# Sheet4.net
KiCad netlist of a schematic drawn in Altium Designer
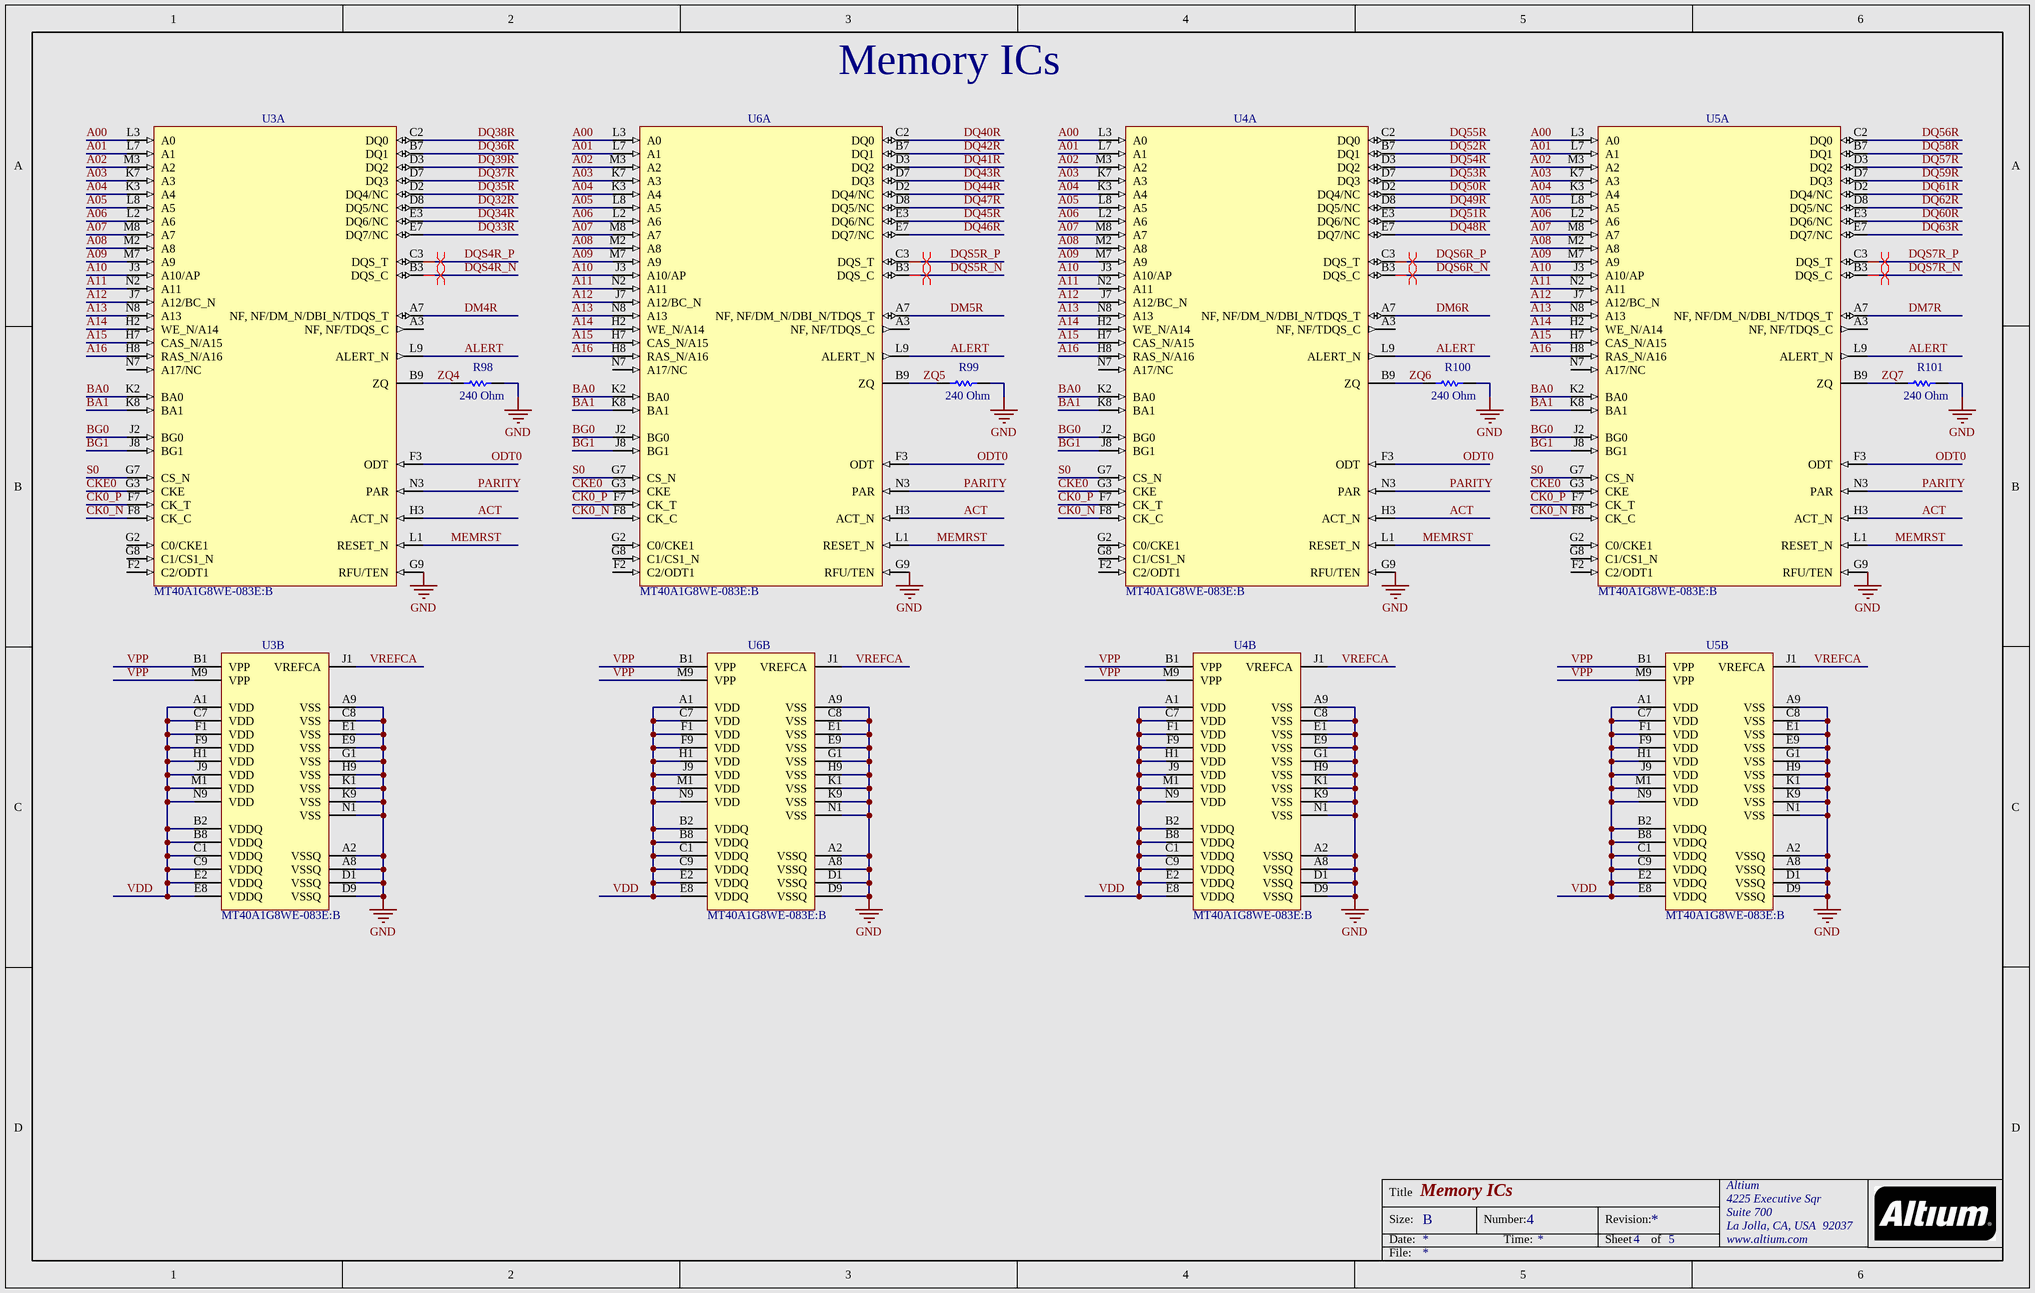
[diagram p0: Sheet4.SchDoc]

(export (version "E")
  (design (tool "Eeschema 10.0.6"))
  (components
    (comp (ref "R98")
      (value "ERJ-2GEJ241x")
      (footprint "RESC1005X40X25ML05T05")
      (description "Chip Resistor, 240 Ohm, +/- 5%, 100 mW, -55 to 155 degC, 0402 (1005 Metric), RoHS, Tape and Reel")
      (fields
        (field (name "RESISTANCE") "240 Ohm")
        (field (name "TOLERANCE") "5%")
        (field (name "MANUFACTURER") "Basic Passives")
      )
      (libsource (lib "Altium Content Vault") (part "CMP-2002-00493-3"))
    )
    (comp (ref "R99")
      (value "ERJ-2GEJ241x")
      (footprint "RESC1005X40X25ML05T05")
      (description "Chip Resistor, 240 Ohm, +/- 5%, 100 mW, -55 to 155 degC, 0402 (1005 Metric), RoHS, Tape and Reel")
      (fields
        (field (name "RESISTANCE") "240 Ohm")
        (field (name "TOLERANCE") "5%")
        (field (name "MANUFACTURER") "Basic Passives")
      )
      (libsource (lib "Altium Content Vault") (part "CMP-2002-00493-3"))
    )
    (comp (ref "R100")
      (value "ERJ-2GEJ241x")
      (footprint "RESC1005X40X25ML05T05")
      (description "Chip Resistor, 240 Ohm, +/- 5%, 100 mW, -55 to 155 degC, 0402 (1005 Metric), RoHS, Tape and Reel")
      (fields
        (field (name "RESISTANCE") "240 Ohm")
        (field (name "TOLERANCE") "5%")
        (field (name "MANUFACTURER") "Basic Passives")
      )
      (libsource (lib "Altium Content Vault") (part "CMP-2002-00493-3"))
    )
    (comp (ref "R101")
      (value "ERJ-2GEJ241x")
      (footprint "RESC1005X40X25ML05T05")
      (description "Chip Resistor, 240 Ohm, +/- 5%, 100 mW, -55 to 155 degC, 0402 (1005 Metric), RoHS, Tape and Reel")
      (fields
        (field (name "RESISTANCE") "240 Ohm")
        (field (name "TOLERANCE") "5%")
        (field (name "MANUFACTURER") "Basic Passives")
      )
      (libsource (lib "Altium Content Vault") (part "CMP-2002-00493-3"))
    )
    (comp (ref "U3")
      (value "MT40A1G8WE-083E:B")
      (footprint "MICT-WE-78")
      (description "8 Gb DDR4 SDRAM, 1 Gig x 8, 1.2 V, 0 to 95 degC, 78-Ball FBGA (WE), RoHS")
      (libsource (lib "Altium Content Vault") (part "CMP-1738-00001-1"))
    )
    (comp (ref "U4")
      (value "MT40A1G8WE-083E:B")
      (footprint "MICT-WE-78")
      (description "8 Gb DDR4 SDRAM, 1 Gig x 8, 1.2 V, 0 to 95 degC, 78-Ball FBGA (WE), RoHS")
      (libsource (lib "Altium Content Vault") (part "CMP-1738-00001-1"))
    )
    (comp (ref "U5")
      (value "MT40A1G8WE-083E:B")
      (footprint "MICT-WE-78")
      (description "8 Gb DDR4 SDRAM, 1 Gig x 8, 1.2 V, 0 to 95 degC, 78-Ball FBGA (WE), RoHS")
      (libsource (lib "Altium Content Vault") (part "CMP-1738-00001-1"))
    )
    (comp (ref "U6")
      (value "MT40A1G8WE-083E:B")
      (footprint "MICT-WE-78")
      (description "8 Gb DDR4 SDRAM, 1 Gig x 8, 1.2 V, 0 to 95 degC, 78-Ball FBGA (WE), RoHS")
      (libsource (lib "Altium Content Vault") (part "CMP-1738-00001-1"))
    )
  )
  (nets
    (net (code "1") (name "/A00") (class "Default")
      (node (ref "U3") (pin "L3") (pinfunction "A0_L3") (pintype "input"))
      (node (ref "U4") (pin "L3") (pinfunction "A0_L3") (pintype "input"))
      (node (ref "U5") (pin "L3") (pinfunction "A0_L3") (pintype "input"))
      (node (ref "U6") (pin "L3") (pinfunction "A0_L3") (pintype "input"))
    )
    (net (code "2") (name "/A01") (class "Default")
      (node (ref "U3") (pin "L7") (pinfunction "A1_L7") (pintype "input"))
      (node (ref "U4") (pin "L7") (pinfunction "A1_L7") (pintype "input"))
      (node (ref "U5") (pin "L7") (pinfunction "A1_L7") (pintype "input"))
      (node (ref "U6") (pin "L7") (pinfunction "A1_L7") (pintype "input"))
    )
    (net (code "3") (name "/A02") (class "Default")
      (node (ref "U3") (pin "M3") (pinfunction "A2_M3") (pintype "input"))
      (node (ref "U4") (pin "M3") (pinfunction "A2_M3") (pintype "input"))
      (node (ref "U5") (pin "M3") (pinfunction "A2_M3") (pintype "input"))
      (node (ref "U6") (pin "M3") (pinfunction "A2_M3") (pintype "input"))
    )
    (net (code "4") (name "/A03") (class "Default")
      (node (ref "U3") (pin "K7") (pinfunction "A3_K7") (pintype "input"))
      (node (ref "U4") (pin "K7") (pinfunction "A3_K7") (pintype "input"))
      (node (ref "U5") (pin "K7") (pinfunction "A3_K7") (pintype "input"))
      (node (ref "U6") (pin "K7") (pinfunction "A3_K7") (pintype "input"))
    )
    (net (code "5") (name "/A04") (class "Default")
      (node (ref "U3") (pin "K3") (pinfunction "A4_K3") (pintype "input"))
      (node (ref "U4") (pin "K3") (pinfunction "A4_K3") (pintype "input"))
      (node (ref "U5") (pin "K3") (pinfunction "A4_K3") (pintype "input"))
      (node (ref "U6") (pin "K3") (pinfunction "A4_K3") (pintype "input"))
    )
    (net (code "6") (name "/A05") (class "Default")
      (node (ref "U3") (pin "L8") (pinfunction "A5_L8") (pintype "input"))
      (node (ref "U4") (pin "L8") (pinfunction "A5_L8") (pintype "input"))
      (node (ref "U5") (pin "L8") (pinfunction "A5_L8") (pintype "input"))
      (node (ref "U6") (pin "L8") (pinfunction "A5_L8") (pintype "input"))
    )
    (net (code "7") (name "/A06") (class "Default")
      (node (ref "U3") (pin "L2") (pinfunction "A6_L2") (pintype "input"))
      (node (ref "U4") (pin "L2") (pinfunction "A6_L2") (pintype "input"))
      (node (ref "U5") (pin "L2") (pinfunction "A6_L2") (pintype "input"))
      (node (ref "U6") (pin "L2") (pinfunction "A6_L2") (pintype "input"))
    )
    (net (code "8") (name "/A07") (class "Default")
      (node (ref "U3") (pin "M8") (pinfunction "A7_M8") (pintype "input"))
      (node (ref "U4") (pin "M8") (pinfunction "A7_M8") (pintype "input"))
      (node (ref "U5") (pin "M8") (pinfunction "A7_M8") (pintype "input"))
      (node (ref "U6") (pin "M8") (pinfunction "A7_M8") (pintype "input"))
    )
    (net (code "9") (name "/A08") (class "Default")
      (node (ref "U3") (pin "M2") (pinfunction "A8_M2") (pintype "input"))
      (node (ref "U4") (pin "M2") (pinfunction "A8_M2") (pintype "input"))
      (node (ref "U5") (pin "M2") (pinfunction "A8_M2") (pintype "input"))
      (node (ref "U6") (pin "M2") (pinfunction "A8_M2") (pintype "input"))
    )
    (net (code "10") (name "/A09") (class "Default")
      (node (ref "U3") (pin "M7") (pinfunction "A9_M7") (pintype "input"))
      (node (ref "U4") (pin "M7") (pinfunction "A9_M7") (pintype "input"))
      (node (ref "U5") (pin "M7") (pinfunction "A9_M7") (pintype "input"))
      (node (ref "U6") (pin "M7") (pinfunction "A9_M7") (pintype "input"))
    )
    (net (code "11") (name "/A10") (class "Default")
      (node (ref "U3") (pin "J3") (pinfunction "A10/AP_J3") (pintype "input"))
      (node (ref "U4") (pin "J3") (pinfunction "A10/AP_J3") (pintype "input"))
      (node (ref "U5") (pin "J3") (pinfunction "A10/AP_J3") (pintype "input"))
      (node (ref "U6") (pin "J3") (pinfunction "A10/AP_J3") (pintype "input"))
    )
    (net (code "12") (name "/A11") (class "Default")
      (node (ref "U3") (pin "N2") (pinfunction "A11_N2") (pintype "input"))
      (node (ref "U4") (pin "N2") (pinfunction "A11_N2") (pintype "input"))
      (node (ref "U5") (pin "N2") (pinfunction "A11_N2") (pintype "input"))
      (node (ref "U6") (pin "N2") (pinfunction "A11_N2") (pintype "input"))
    )
    (net (code "13") (name "/A12") (class "Default")
      (node (ref "U3") (pin "J7") (pinfunction "A12/BC_N_J7") (pintype "input"))
      (node (ref "U4") (pin "J7") (pinfunction "A12/BC_N_J7") (pintype "input"))
      (node (ref "U5") (pin "J7") (pinfunction "A12/BC_N_J7") (pintype "input"))
      (node (ref "U6") (pin "J7") (pinfunction "A12/BC_N_J7") (pintype "input"))
    )
    (net (code "14") (name "/A13") (class "Default")
      (node (ref "U3") (pin "N8") (pinfunction "A13_N8") (pintype "input"))
      (node (ref "U4") (pin "N8") (pinfunction "A13_N8") (pintype "input"))
      (node (ref "U5") (pin "N8") (pinfunction "A13_N8") (pintype "input"))
      (node (ref "U6") (pin "N8") (pinfunction "A13_N8") (pintype "input"))
    )
    (net (code "15") (name "/A14") (class "Default")
      (node (ref "U3") (pin "H2") (pinfunction "WE_N/A14_H2") (pintype "input"))
      (node (ref "U4") (pin "H2") (pinfunction "WE_N/A14_H2") (pintype "input"))
      (node (ref "U5") (pin "H2") (pinfunction "WE_N/A14_H2") (pintype "input"))
      (node (ref "U6") (pin "H2") (pinfunction "WE_N/A14_H2") (pintype "input"))
    )
    (net (code "16") (name "/A15") (class "Default")
      (node (ref "U3") (pin "H7") (pinfunction "CAS_N/A15_H7") (pintype "input"))
      (node (ref "U4") (pin "H7") (pinfunction "CAS_N/A15_H7") (pintype "input"))
      (node (ref "U5") (pin "H7") (pinfunction "CAS_N/A15_H7") (pintype "input"))
      (node (ref "U6") (pin "H7") (pinfunction "CAS_N/A15_H7") (pintype "input"))
    )
    (net (code "17") (name "/A16") (class "Default")
      (node (ref "U3") (pin "H8") (pinfunction "RAS_N/A16_H8") (pintype "input"))
      (node (ref "U4") (pin "H8") (pinfunction "RAS_N/A16_H8") (pintype "input"))
      (node (ref "U5") (pin "H8") (pinfunction "RAS_N/A16_H8") (pintype "input"))
      (node (ref "U6") (pin "H8") (pinfunction "RAS_N/A16_H8") (pintype "input"))
    )
    (net (code "18") (name "/ACT") (class "Default")
      (node (ref "U3") (pin "H3") (pinfunction "ACT_N_H3") (pintype "input"))
      (node (ref "U4") (pin "H3") (pinfunction "ACT_N_H3") (pintype "input"))
      (node (ref "U5") (pin "H3") (pinfunction "ACT_N_H3") (pintype "input"))
      (node (ref "U6") (pin "H3") (pinfunction "ACT_N_H3") (pintype "input"))
    )
    (net (code "19") (name "/ALERT") (class "Default")
      (node (ref "U3") (pin "L9") (pinfunction "ALERT_N_L9") (pintype "output"))
      (node (ref "U4") (pin "L9") (pinfunction "ALERT_N_L9") (pintype "output"))
      (node (ref "U5") (pin "L9") (pinfunction "ALERT_N_L9") (pintype "output"))
      (node (ref "U6") (pin "L9") (pinfunction "ALERT_N_L9") (pintype "output"))
    )
    (net (code "20") (name "/BA0") (class "Default")
      (node (ref "U3") (pin "K2") (pinfunction "BA0_K2") (pintype "input"))
      (node (ref "U4") (pin "K2") (pinfunction "BA0_K2") (pintype "input"))
      (node (ref "U5") (pin "K2") (pinfunction "BA0_K2") (pintype "input"))
      (node (ref "U6") (pin "K2") (pinfunction "BA0_K2") (pintype "input"))
    )
    (net (code "21") (name "/BA1") (class "Default")
      (node (ref "U3") (pin "K8") (pinfunction "BA1_K8") (pintype "input"))
      (node (ref "U4") (pin "K8") (pinfunction "BA1_K8") (pintype "input"))
      (node (ref "U5") (pin "K8") (pinfunction "BA1_K8") (pintype "input"))
      (node (ref "U6") (pin "K8") (pinfunction "BA1_K8") (pintype "input"))
    )
    (net (code "22") (name "/BG0") (class "Default")
      (node (ref "U3") (pin "J2") (pinfunction "BG0_J2") (pintype "input"))
      (node (ref "U4") (pin "J2") (pinfunction "BG0_J2") (pintype "input"))
      (node (ref "U5") (pin "J2") (pinfunction "BG0_J2") (pintype "input"))
      (node (ref "U6") (pin "J2") (pinfunction "BG0_J2") (pintype "input"))
    )
    (net (code "23") (name "/BG1") (class "Default")
      (node (ref "U3") (pin "J8") (pinfunction "BG1_J8") (pintype "input"))
      (node (ref "U4") (pin "J8") (pinfunction "BG1_J8") (pintype "input"))
      (node (ref "U5") (pin "J8") (pinfunction "BG1_J8") (pintype "input"))
      (node (ref "U6") (pin "J8") (pinfunction "BG1_J8") (pintype "input"))
    )
    (net (code "24") (name "/CK0_N") (class "Default")
      (node (ref "U3") (pin "F8") (pinfunction "CK_C_F8") (pintype "input"))
      (node (ref "U4") (pin "F8") (pinfunction "CK_C_F8") (pintype "input"))
      (node (ref "U5") (pin "F8") (pinfunction "CK_C_F8") (pintype "input"))
      (node (ref "U6") (pin "F8") (pinfunction "CK_C_F8") (pintype "input"))
    )
    (net (code "25") (name "/CK0_P") (class "Default")
      (node (ref "U3") (pin "F7") (pinfunction "CK_T_F7") (pintype "input"))
      (node (ref "U4") (pin "F7") (pinfunction "CK_T_F7") (pintype "input"))
      (node (ref "U5") (pin "F7") (pinfunction "CK_T_F7") (pintype "input"))
      (node (ref "U6") (pin "F7") (pinfunction "CK_T_F7") (pintype "input"))
    )
    (net (code "26") (name "/CKE0") (class "Default")
      (node (ref "U3") (pin "G3") (pinfunction "CKE_G3") (pintype "input"))
      (node (ref "U4") (pin "G3") (pinfunction "CKE_G3") (pintype "input"))
      (node (ref "U5") (pin "G3") (pinfunction "CKE_G3") (pintype "input"))
      (node (ref "U6") (pin "G3") (pinfunction "CKE_G3") (pintype "input"))
    )
    (net (code "27") (name "/DM4R") (class "Default")
      (node (ref "U3") (pin "A7") (pinfunction "NF,_NF/DM_N/DBI_N/TDQS_T_A7") (pintype "bidirectional"))
    )
    (net (code "28") (name "/DM5R") (class "Default")
      (node (ref "U6") (pin "A7") (pinfunction "NF,_NF/DM_N/DBI_N/TDQS_T_A7") (pintype "bidirectional"))
    )
    (net (code "29") (name "/DM6R") (class "Default")
      (node (ref "U4") (pin "A7") (pinfunction "NF,_NF/DM_N/DBI_N/TDQS_T_A7") (pintype "bidirectional"))
    )
    (net (code "30") (name "/DM7R") (class "Default")
      (node (ref "U5") (pin "A7") (pinfunction "NF,_NF/DM_N/DBI_N/TDQS_T_A7") (pintype "bidirectional"))
    )
    (net (code "31") (name "/DQ32R") (class "Default")
      (node (ref "U3") (pin "D8") (pinfunction "DQ5/NC_D8") (pintype "bidirectional"))
    )
    (net (code "32") (name "/DQ33R") (class "Default")
      (node (ref "U3") (pin "E7") (pinfunction "DQ7/NC_E7") (pintype "bidirectional"))
    )
    (net (code "33") (name "/DQ34R") (class "Default")
      (node (ref "U3") (pin "E3") (pinfunction "DQ6/NC_E3") (pintype "bidirectional"))
    )
    (net (code "34") (name "/DQ35R") (class "Default")
      (node (ref "U3") (pin "D2") (pinfunction "DQ4/NC_D2") (pintype "bidirectional"))
    )
    (net (code "35") (name "/DQ36R") (class "Default")
      (node (ref "U3") (pin "B7") (pinfunction "DQ1_B7") (pintype "bidirectional"))
    )
    (net (code "36") (name "/DQ37R") (class "Default")
      (node (ref "U3") (pin "D7") (pinfunction "DQ3_D7") (pintype "bidirectional"))
    )
    (net (code "37") (name "/DQ38R") (class "Default")
      (node (ref "U3") (pin "C2") (pinfunction "DQ0_C2") (pintype "bidirectional"))
    )
    (net (code "38") (name "/DQ39R") (class "Default")
      (node (ref "U3") (pin "D3") (pinfunction "DQ2_D3") (pintype "bidirectional"))
    )
    (net (code "39") (name "/DQ40R") (class "Default")
      (node (ref "U6") (pin "C2") (pinfunction "DQ0_C2") (pintype "bidirectional"))
    )
    (net (code "40") (name "/DQ41R") (class "Default")
      (node (ref "U6") (pin "D3") (pinfunction "DQ2_D3") (pintype "bidirectional"))
    )
    (net (code "41") (name "/DQ42R") (class "Default")
      (node (ref "U6") (pin "B7") (pinfunction "DQ1_B7") (pintype "bidirectional"))
    )
    (net (code "42") (name "/DQ43R") (class "Default")
      (node (ref "U6") (pin "D7") (pinfunction "DQ3_D7") (pintype "bidirectional"))
    )
    (net (code "43") (name "/DQ44R") (class "Default")
      (node (ref "U6") (pin "D2") (pinfunction "DQ4/NC_D2") (pintype "bidirectional"))
    )
    (net (code "44") (name "/DQ45R") (class "Default")
      (node (ref "U6") (pin "E3") (pinfunction "DQ6/NC_E3") (pintype "bidirectional"))
    )
    (net (code "45") (name "/DQ46R") (class "Default")
      (node (ref "U6") (pin "E7") (pinfunction "DQ7/NC_E7") (pintype "bidirectional"))
    )
    (net (code "46") (name "/DQ47R") (class "Default")
      (node (ref "U6") (pin "D8") (pinfunction "DQ5/NC_D8") (pintype "bidirectional"))
    )
    (net (code "47") (name "/DQ48R") (class "Default")
      (node (ref "U4") (pin "E7") (pinfunction "DQ7/NC_E7") (pintype "bidirectional"))
    )
    (net (code "48") (name "/DQ49R") (class "Default")
      (node (ref "U4") (pin "D8") (pinfunction "DQ5/NC_D8") (pintype "bidirectional"))
    )
    (net (code "49") (name "/DQ50R") (class "Default")
      (node (ref "U4") (pin "D2") (pinfunction "DQ4/NC_D2") (pintype "bidirectional"))
    )
    (net (code "50") (name "/DQ51R") (class "Default")
      (node (ref "U4") (pin "E3") (pinfunction "DQ6/NC_E3") (pintype "bidirectional"))
    )
    (net (code "51") (name "/DQ52R") (class "Default")
      (node (ref "U4") (pin "B7") (pinfunction "DQ1_B7") (pintype "bidirectional"))
    )
    (net (code "52") (name "/DQ53R") (class "Default")
      (node (ref "U4") (pin "D7") (pinfunction "DQ3_D7") (pintype "bidirectional"))
    )
    (net (code "53") (name "/DQ54R") (class "Default")
      (node (ref "U4") (pin "D3") (pinfunction "DQ2_D3") (pintype "bidirectional"))
    )
    (net (code "54") (name "/DQ55R") (class "Default")
      (node (ref "U4") (pin "C2") (pinfunction "DQ0_C2") (pintype "bidirectional"))
    )
    (net (code "55") (name "/DQ56R") (class "Default")
      (node (ref "U5") (pin "C2") (pinfunction "DQ0_C2") (pintype "bidirectional"))
    )
    (net (code "56") (name "/DQ57R") (class "Default")
      (node (ref "U5") (pin "D3") (pinfunction "DQ2_D3") (pintype "bidirectional"))
    )
    (net (code "57") (name "/DQ58R") (class "Default")
      (node (ref "U5") (pin "B7") (pinfunction "DQ1_B7") (pintype "bidirectional"))
    )
    (net (code "58") (name "/DQ59R") (class "Default")
      (node (ref "U5") (pin "D7") (pinfunction "DQ3_D7") (pintype "bidirectional"))
    )
    (net (code "59") (name "/DQ60R") (class "Default")
      (node (ref "U5") (pin "E3") (pinfunction "DQ6/NC_E3") (pintype "bidirectional"))
    )
    (net (code "60") (name "/DQ61R") (class "Default")
      (node (ref "U5") (pin "D2") (pinfunction "DQ4/NC_D2") (pintype "bidirectional"))
    )
    (net (code "61") (name "/DQ62R") (class "Default")
      (node (ref "U5") (pin "D8") (pinfunction "DQ5/NC_D8") (pintype "bidirectional"))
    )
    (net (code "62") (name "/DQ63R") (class "Default")
      (node (ref "U5") (pin "E7") (pinfunction "DQ7/NC_E7") (pintype "bidirectional"))
    )
    (net (code "63") (name "/DQS4R_N") (class "Default")
      (node (ref "U3") (pin "B3") (pinfunction "DQS_C_B3") (pintype "bidirectional"))
    )
    (net (code "64") (name "/DQS4R_P") (class "Default")
      (node (ref "U3") (pin "C3") (pinfunction "DQS_T_C3") (pintype "bidirectional"))
    )
    (net (code "65") (name "/DQS5R_N") (class "Default")
      (node (ref "U6") (pin "B3") (pinfunction "DQS_C_B3") (pintype "bidirectional"))
    )
    (net (code "66") (name "/DQS5R_P") (class "Default")
      (node (ref "U6") (pin "C3") (pinfunction "DQS_T_C3") (pintype "bidirectional"))
    )
    (net (code "67") (name "/DQS6R_N") (class "Default")
      (node (ref "U4") (pin "B3") (pinfunction "DQS_C_B3") (pintype "bidirectional"))
    )
    (net (code "68") (name "/DQS6R_P") (class "Default")
      (node (ref "U4") (pin "C3") (pinfunction "DQS_T_C3") (pintype "bidirectional"))
    )
    (net (code "69") (name "/DQS7R_N") (class "Default")
      (node (ref "U5") (pin "B3") (pinfunction "DQS_C_B3") (pintype "bidirectional"))
    )
    (net (code "70") (name "/DQS7R_P") (class "Default")
      (node (ref "U5") (pin "C3") (pinfunction "DQS_T_C3") (pintype "bidirectional"))
    )
    (net (code "71") (name "/MEMRST") (class "Default")
      (node (ref "U3") (pin "L1") (pinfunction "RESET_N_L1") (pintype "input"))
      (node (ref "U4") (pin "L1") (pinfunction "RESET_N_L1") (pintype "input"))
      (node (ref "U5") (pin "L1") (pinfunction "RESET_N_L1") (pintype "input"))
      (node (ref "U6") (pin "L1") (pinfunction "RESET_N_L1") (pintype "input"))
    )
    (net (code "72") (name "/ODT0") (class "Default")
      (node (ref "U3") (pin "F3") (pinfunction "ODT_F3") (pintype "input"))
      (node (ref "U4") (pin "F3") (pinfunction "ODT_F3") (pintype "input"))
      (node (ref "U5") (pin "F3") (pinfunction "ODT_F3") (pintype "input"))
      (node (ref "U6") (pin "F3") (pinfunction "ODT_F3") (pintype "input"))
    )
    (net (code "73") (name "/PARITY") (class "Default")
      (node (ref "U3") (pin "N3") (pinfunction "PAR_N3") (pintype "input"))
      (node (ref "U4") (pin "N3") (pinfunction "PAR_N3") (pintype "input"))
      (node (ref "U5") (pin "N3") (pinfunction "PAR_N3") (pintype "input"))
      (node (ref "U6") (pin "N3") (pinfunction "PAR_N3") (pintype "input"))
    )
    (net (code "74") (name "/S0") (class "Default")
      (node (ref "U3") (pin "G7") (pinfunction "CS_N_G7") (pintype "input"))
      (node (ref "U4") (pin "G7") (pinfunction "CS_N_G7") (pintype "input"))
      (node (ref "U5") (pin "G7") (pinfunction "CS_N_G7") (pintype "input"))
      (node (ref "U6") (pin "G7") (pinfunction "CS_N_G7") (pintype "input"))
    )
    (net (code "75") (name "/VDD") (class "Default")
      (node (ref "U3") (pin "A1") (pinfunction "VDD_A1") (pintype "power_in"))
      (node (ref "U3") (pin "B2") (pinfunction "VDDQ_B2") (pintype "power_in"))
      (node (ref "U3") (pin "B8") (pinfunction "VDDQ_B8") (pintype "power_in"))
      (node (ref "U3") (pin "C1") (pinfunction "VDDQ_C1") (pintype "power_in"))
      (node (ref "U3") (pin "C7") (pinfunction "VDD_C7") (pintype "power_in"))
      (node (ref "U3") (pin "C9") (pinfunction "VDDQ_C9") (pintype "power_in"))
      (node (ref "U3") (pin "E2") (pinfunction "VDDQ_E2") (pintype "power_in"))
      (node (ref "U3") (pin "E8") (pinfunction "VDDQ_E8") (pintype "power_in"))
      (node (ref "U3") (pin "F1") (pinfunction "VDD_F1") (pintype "power_in"))
      (node (ref "U3") (pin "F9") (pinfunction "VDD_F9") (pintype "power_in"))
      (node (ref "U3") (pin "H1") (pinfunction "VDD_H1") (pintype "power_in"))
      (node (ref "U3") (pin "J9") (pinfunction "VDD_J9") (pintype "power_in"))
      (node (ref "U3") (pin "M1") (pinfunction "VDD_M1") (pintype "power_in"))
      (node (ref "U3") (pin "N9") (pinfunction "VDD_N9") (pintype "power_in"))
      (node (ref "U4") (pin "A1") (pinfunction "VDD_A1") (pintype "power_in"))
      (node (ref "U4") (pin "B2") (pinfunction "VDDQ_B2") (pintype "power_in"))
      (node (ref "U4") (pin "B8") (pinfunction "VDDQ_B8") (pintype "power_in"))
      (node (ref "U4") (pin "C1") (pinfunction "VDDQ_C1") (pintype "power_in"))
      (node (ref "U4") (pin "C7") (pinfunction "VDD_C7") (pintype "power_in"))
      (node (ref "U4") (pin "C9") (pinfunction "VDDQ_C9") (pintype "power_in"))
      (node (ref "U4") (pin "E2") (pinfunction "VDDQ_E2") (pintype "power_in"))
      (node (ref "U4") (pin "E8") (pinfunction "VDDQ_E8") (pintype "power_in"))
      (node (ref "U4") (pin "F1") (pinfunction "VDD_F1") (pintype "power_in"))
      (node (ref "U4") (pin "F9") (pinfunction "VDD_F9") (pintype "power_in"))
      (node (ref "U4") (pin "H1") (pinfunction "VDD_H1") (pintype "power_in"))
      (node (ref "U4") (pin "J9") (pinfunction "VDD_J9") (pintype "power_in"))
      (node (ref "U4") (pin "M1") (pinfunction "VDD_M1") (pintype "power_in"))
      (node (ref "U4") (pin "N9") (pinfunction "VDD_N9") (pintype "power_in"))
      (node (ref "U5") (pin "A1") (pinfunction "VDD_A1") (pintype "power_in"))
      (node (ref "U5") (pin "B2") (pinfunction "VDDQ_B2") (pintype "power_in"))
      (node (ref "U5") (pin "B8") (pinfunction "VDDQ_B8") (pintype "power_in"))
      (node (ref "U5") (pin "C1") (pinfunction "VDDQ_C1") (pintype "power_in"))
      (node (ref "U5") (pin "C7") (pinfunction "VDD_C7") (pintype "power_in"))
      (node (ref "U5") (pin "C9") (pinfunction "VDDQ_C9") (pintype "power_in"))
      (node (ref "U5") (pin "E2") (pinfunction "VDDQ_E2") (pintype "power_in"))
      (node (ref "U5") (pin "E8") (pinfunction "VDDQ_E8") (pintype "power_in"))
      (node (ref "U5") (pin "F1") (pinfunction "VDD_F1") (pintype "power_in"))
      (node (ref "U5") (pin "F9") (pinfunction "VDD_F9") (pintype "power_in"))
      (node (ref "U5") (pin "H1") (pinfunction "VDD_H1") (pintype "power_in"))
      (node (ref "U5") (pin "J9") (pinfunction "VDD_J9") (pintype "power_in"))
      (node (ref "U5") (pin "M1") (pinfunction "VDD_M1") (pintype "power_in"))
      (node (ref "U5") (pin "N9") (pinfunction "VDD_N9") (pintype "power_in"))
      (node (ref "U6") (pin "A1") (pinfunction "VDD_A1") (pintype "power_in"))
      (node (ref "U6") (pin "B2") (pinfunction "VDDQ_B2") (pintype "power_in"))
      (node (ref "U6") (pin "B8") (pinfunction "VDDQ_B8") (pintype "power_in"))
      (node (ref "U6") (pin "C1") (pinfunction "VDDQ_C1") (pintype "power_in"))
      (node (ref "U6") (pin "C7") (pinfunction "VDD_C7") (pintype "power_in"))
      (node (ref "U6") (pin "C9") (pinfunction "VDDQ_C9") (pintype "power_in"))
      (node (ref "U6") (pin "E2") (pinfunction "VDDQ_E2") (pintype "power_in"))
      (node (ref "U6") (pin "E8") (pinfunction "VDDQ_E8") (pintype "power_in"))
      (node (ref "U6") (pin "F1") (pinfunction "VDD_F1") (pintype "power_in"))
      (node (ref "U6") (pin "F9") (pinfunction "VDD_F9") (pintype "power_in"))
      (node (ref "U6") (pin "H1") (pinfunction "VDD_H1") (pintype "power_in"))
      (node (ref "U6") (pin "J9") (pinfunction "VDD_J9") (pintype "power_in"))
      (node (ref "U6") (pin "M1") (pinfunction "VDD_M1") (pintype "power_in"))
      (node (ref "U6") (pin "N9") (pinfunction "VDD_N9") (pintype "power_in"))
    )
    (net (code "76") (name "/VPP") (class "Default")
      (node (ref "U3") (pin "B1") (pinfunction "VPP_B1") (pintype "power_in"))
      (node (ref "U3") (pin "M9") (pinfunction "VPP_M9") (pintype "power_in"))
      (node (ref "U4") (pin "B1") (pinfunction "VPP_B1") (pintype "power_in"))
      (node (ref "U4") (pin "M9") (pinfunction "VPP_M9") (pintype "power_in"))
      (node (ref "U5") (pin "B1") (pinfunction "VPP_B1") (pintype "power_in"))
      (node (ref "U5") (pin "M9") (pinfunction "VPP_M9") (pintype "power_in"))
      (node (ref "U6") (pin "B1") (pinfunction "VPP_B1") (pintype "power_in"))
      (node (ref "U6") (pin "M9") (pinfunction "VPP_M9") (pintype "power_in"))
    )
    (net (code "77") (name "/VREFCA") (class "Default")
      (node (ref "U3") (pin "J1") (pinfunction "VREFCA_J1") (pintype "passive"))
      (node (ref "U4") (pin "J1") (pinfunction "VREFCA_J1") (pintype "passive"))
      (node (ref "U5") (pin "J1") (pinfunction "VREFCA_J1") (pintype "passive"))
      (node (ref "U6") (pin "J1") (pinfunction "VREFCA_J1") (pintype "passive"))
    )
    (net (code "78") (name "/ZQ4") (class "Default")
      (node (ref "R98") (pin "2") (pinfunction "2_2") (pintype "passive"))
      (node (ref "U3") (pin "B9") (pinfunction "ZQ_B9") (pintype "passive"))
    )
    (net (code "79") (name "/ZQ5") (class "Default")
      (node (ref "R99") (pin "2") (pinfunction "2_2") (pintype "passive"))
      (node (ref "U6") (pin "B9") (pinfunction "ZQ_B9") (pintype "passive"))
    )
    (net (code "80") (name "/ZQ6") (class "Default")
      (node (ref "R100") (pin "2") (pinfunction "2_2") (pintype "passive"))
      (node (ref "U4") (pin "B9") (pinfunction "ZQ_B9") (pintype "passive"))
    )
    (net (code "81") (name "/ZQ7") (class "Default")
      (node (ref "R101") (pin "2") (pinfunction "2_2") (pintype "passive"))
      (node (ref "U5") (pin "B9") (pinfunction "ZQ_B9") (pintype "passive"))
    )
    (net (code "82") (name "GND") (class "Default")
      (node (ref "R100") (pin "1") (pinfunction "1_1") (pintype "passive"))
      (node (ref "R101") (pin "1") (pinfunction "1_1") (pintype "passive"))
      (node (ref "R98") (pin "1") (pinfunction "1_1") (pintype "passive"))
      (node (ref "R99") (pin "1") (pinfunction "1_1") (pintype "passive"))
      (node (ref "U3") (pin "A2") (pinfunction "VSSQ_A2") (pintype "power_in"))
      (node (ref "U3") (pin "A8") (pinfunction "VSSQ_A8") (pintype "power_in"))
      (node (ref "U3") (pin "A9") (pinfunction "VSS_A9") (pintype "power_in"))
      (node (ref "U3") (pin "C8") (pinfunction "VSS_C8") (pintype "power_in"))
      (node (ref "U3") (pin "D1") (pinfunction "VSSQ_D1") (pintype "power_in"))
      (node (ref "U3") (pin "D9") (pinfunction "VSSQ_D9") (pintype "power_in"))
      (node (ref "U3") (pin "E1") (pinfunction "VSS_E1") (pintype "power_in"))
      (node (ref "U3") (pin "E9") (pinfunction "VSS_E9") (pintype "power_in"))
      (node (ref "U3") (pin "G1") (pinfunction "VSS_G1") (pintype "power_in"))
      (node (ref "U3") (pin "G9") (pinfunction "RFU/TEN_G9") (pintype "input"))
      (node (ref "U3") (pin "H9") (pinfunction "VSS_H9") (pintype "power_in"))
      (node (ref "U3") (pin "K1") (pinfunction "VSS_K1") (pintype "power_in"))
      (node (ref "U3") (pin "K9") (pinfunction "VSS_K9") (pintype "power_in"))
      (node (ref "U3") (pin "N1") (pinfunction "VSS_N1") (pintype "power_in"))
      (node (ref "U4") (pin "A2") (pinfunction "VSSQ_A2") (pintype "power_in"))
      (node (ref "U4") (pin "A8") (pinfunction "VSSQ_A8") (pintype "power_in"))
      (node (ref "U4") (pin "A9") (pinfunction "VSS_A9") (pintype "power_in"))
      (node (ref "U4") (pin "C8") (pinfunction "VSS_C8") (pintype "power_in"))
      (node (ref "U4") (pin "D1") (pinfunction "VSSQ_D1") (pintype "power_in"))
      (node (ref "U4") (pin "D9") (pinfunction "VSSQ_D9") (pintype "power_in"))
      (node (ref "U4") (pin "E1") (pinfunction "VSS_E1") (pintype "power_in"))
      (node (ref "U4") (pin "E9") (pinfunction "VSS_E9") (pintype "power_in"))
      (node (ref "U4") (pin "G1") (pinfunction "VSS_G1") (pintype "power_in"))
      (node (ref "U4") (pin "G9") (pinfunction "RFU/TEN_G9") (pintype "input"))
      (node (ref "U4") (pin "H9") (pinfunction "VSS_H9") (pintype "power_in"))
      (node (ref "U4") (pin "K1") (pinfunction "VSS_K1") (pintype "power_in"))
      (node (ref "U4") (pin "K9") (pinfunction "VSS_K9") (pintype "power_in"))
      (node (ref "U4") (pin "N1") (pinfunction "VSS_N1") (pintype "power_in"))
      (node (ref "U5") (pin "A2") (pinfunction "VSSQ_A2") (pintype "power_in"))
      (node (ref "U5") (pin "A8") (pinfunction "VSSQ_A8") (pintype "power_in"))
      (node (ref "U5") (pin "A9") (pinfunction "VSS_A9") (pintype "power_in"))
      (node (ref "U5") (pin "C8") (pinfunction "VSS_C8") (pintype "power_in"))
      (node (ref "U5") (pin "D1") (pinfunction "VSSQ_D1") (pintype "power_in"))
      (node (ref "U5") (pin "D9") (pinfunction "VSSQ_D9") (pintype "power_in"))
      (node (ref "U5") (pin "E1") (pinfunction "VSS_E1") (pintype "power_in"))
      (node (ref "U5") (pin "E9") (pinfunction "VSS_E9") (pintype "power_in"))
      (node (ref "U5") (pin "G1") (pinfunction "VSS_G1") (pintype "power_in"))
      (node (ref "U5") (pin "G9") (pinfunction "RFU/TEN_G9") (pintype "input"))
      (node (ref "U5") (pin "H9") (pinfunction "VSS_H9") (pintype "power_in"))
      (node (ref "U5") (pin "K1") (pinfunction "VSS_K1") (pintype "power_in"))
      (node (ref "U5") (pin "K9") (pinfunction "VSS_K9") (pintype "power_in"))
      (node (ref "U5") (pin "N1") (pinfunction "VSS_N1") (pintype "power_in"))
      (node (ref "U6") (pin "A2") (pinfunction "VSSQ_A2") (pintype "power_in"))
      (node (ref "U6") (pin "A8") (pinfunction "VSSQ_A8") (pintype "power_in"))
      (node (ref "U6") (pin "A9") (pinfunction "VSS_A9") (pintype "power_in"))
      (node (ref "U6") (pin "C8") (pinfunction "VSS_C8") (pintype "power_in"))
      (node (ref "U6") (pin "D1") (pinfunction "VSSQ_D1") (pintype "power_in"))
      (node (ref "U6") (pin "D9") (pinfunction "VSSQ_D9") (pintype "power_in"))
      (node (ref "U6") (pin "E1") (pinfunction "VSS_E1") (pintype "power_in"))
      (node (ref "U6") (pin "E9") (pinfunction "VSS_E9") (pintype "power_in"))
      (node (ref "U6") (pin "G1") (pinfunction "VSS_G1") (pintype "power_in"))
      (node (ref "U6") (pin "G9") (pinfunction "RFU/TEN_G9") (pintype "input"))
      (node (ref "U6") (pin "H9") (pinfunction "VSS_H9") (pintype "power_in"))
      (node (ref "U6") (pin "K1") (pinfunction "VSS_K1") (pintype "power_in"))
      (node (ref "U6") (pin "K9") (pinfunction "VSS_K9") (pintype "power_in"))
      (node (ref "U6") (pin "N1") (pinfunction "VSS_N1") (pintype "power_in"))
    )
    (net (code "83") (name "unconnected-(U3A-A17{slash}NC-PadN7)") (class "Default")
      (node (ref "U3") (pin "N7") (pinfunction "A17/NC_N7") (pintype "input"))
    )
    (net (code "84") (name "unconnected-(U3A-C0{slash}CKE1-PadG2)") (class "Default")
      (node (ref "U3") (pin "G2") (pinfunction "C0/CKE1_G2") (pintype "input"))
    )
    (net (code "85") (name "unconnected-(U3A-C1{slash}CS1_N-PadG8)") (class "Default")
      (node (ref "U3") (pin "G8") (pinfunction "C1/CS1_N_G8") (pintype "input"))
    )
    (net (code "86") (name "unconnected-(U3A-C2{slash}ODT1-PadF2)") (class "Default")
      (node (ref "U3") (pin "F2") (pinfunction "C2/ODT1_F2") (pintype "input"))
    )
    (net (code "87") (name "unconnected-(U3A-NF,_NF{slash}TDQS_C-PadA3)") (class "Default")
      (node (ref "U3") (pin "A3") (pinfunction "NF,_NF/TDQS_C_A3") (pintype "output"))
    )
    (net (code "88") (name "unconnected-(U4A-A17{slash}NC-PadN7)") (class "Default")
      (node (ref "U4") (pin "N7") (pinfunction "A17/NC_N7") (pintype "input"))
    )
    (net (code "89") (name "unconnected-(U4A-C0{slash}CKE1-PadG2)") (class "Default")
      (node (ref "U4") (pin "G2") (pinfunction "C0/CKE1_G2") (pintype "input"))
    )
    (net (code "90") (name "unconnected-(U4A-C1{slash}CS1_N-PadG8)") (class "Default")
      (node (ref "U4") (pin "G8") (pinfunction "C1/CS1_N_G8") (pintype "input"))
    )
    (net (code "91") (name "unconnected-(U4A-C2{slash}ODT1-PadF2)") (class "Default")
      (node (ref "U4") (pin "F2") (pinfunction "C2/ODT1_F2") (pintype "input"))
    )
    (net (code "92") (name "unconnected-(U4A-NF,_NF{slash}TDQS_C-PadA3)") (class "Default")
      (node (ref "U4") (pin "A3") (pinfunction "NF,_NF/TDQS_C_A3") (pintype "output"))
    )
    (net (code "93") (name "unconnected-(U5A-A17{slash}NC-PadN7)") (class "Default")
      (node (ref "U5") (pin "N7") (pinfunction "A17/NC_N7") (pintype "input"))
    )
    (net (code "94") (name "unconnected-(U5A-C0{slash}CKE1-PadG2)") (class "Default")
      (node (ref "U5") (pin "G2") (pinfunction "C0/CKE1_G2") (pintype "input"))
    )
    (net (code "95") (name "unconnected-(U5A-C1{slash}CS1_N-PadG8)") (class "Default")
      (node (ref "U5") (pin "G8") (pinfunction "C1/CS1_N_G8") (pintype "input"))
    )
    (net (code "96") (name "unconnected-(U5A-C2{slash}ODT1-PadF2)") (class "Default")
      (node (ref "U5") (pin "F2") (pinfunction "C2/ODT1_F2") (pintype "input"))
    )
    (net (code "97") (name "unconnected-(U5A-NF,_NF{slash}TDQS_C-PadA3)") (class "Default")
      (node (ref "U5") (pin "A3") (pinfunction "NF,_NF/TDQS_C_A3") (pintype "output"))
    )
    (net (code "98") (name "unconnected-(U6A-A17{slash}NC-PadN7)") (class "Default")
      (node (ref "U6") (pin "N7") (pinfunction "A17/NC_N7") (pintype "input"))
    )
    (net (code "99") (name "unconnected-(U6A-C0{slash}CKE1-PadG2)") (class "Default")
      (node (ref "U6") (pin "G2") (pinfunction "C0/CKE1_G2") (pintype "input"))
    )
    (net (code "100") (name "unconnected-(U6A-C1{slash}CS1_N-PadG8)") (class "Default")
      (node (ref "U6") (pin "G8") (pinfunction "C1/CS1_N_G8") (pintype "input"))
    )
    (net (code "101") (name "unconnected-(U6A-C2{slash}ODT1-PadF2)") (class "Default")
      (node (ref "U6") (pin "F2") (pinfunction "C2/ODT1_F2") (pintype "input"))
    )
    (net (code "102") (name "unconnected-(U6A-NF,_NF{slash}TDQS_C-PadA3)") (class "Default")
      (node (ref "U6") (pin "A3") (pinfunction "NF,_NF/TDQS_C_A3") (pintype "output"))
    )
  )
)
